# G.net
KiCad netlist of a schematic drawn in Altium Designer
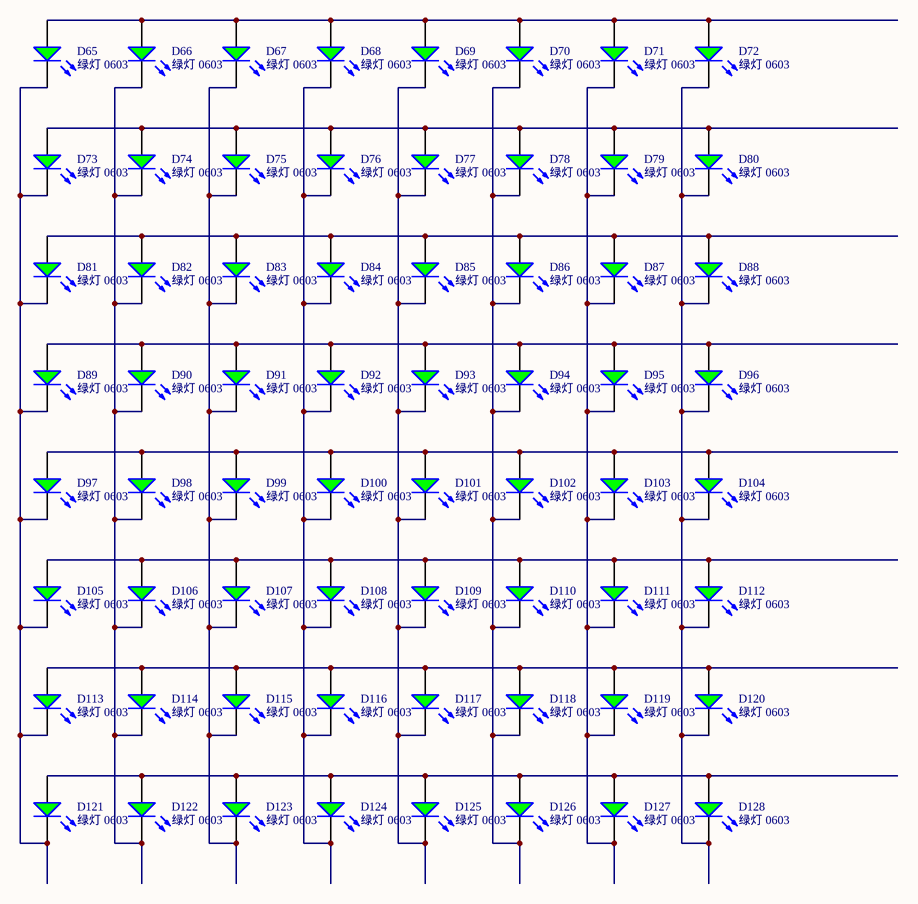
[diagram p0: G.SchDoc]

(export (version "E")
  (design (tool "Eeschema 10.0.6"))
  (components
    (comp (ref "D65")
      (value "绿灯 0603")
      (footprint "0603_LED_S1")
      (description "发光二极管")
      (libsource (lib "Miscellaneous Devices LC") (part "0603 绿灯"))
    )
    (comp (ref "D66")
      (value "绿灯 0603")
      (footprint "0603_LED_S1")
      (description "发光二极管")
      (libsource (lib "Miscellaneous Devices LC") (part "0603 绿灯"))
    )
    (comp (ref "D67")
      (value "绿灯 0603")
      (footprint "0603_LED_S1")
      (description "发光二极管")
      (libsource (lib "Miscellaneous Devices LC") (part "0603 绿灯"))
    )
    (comp (ref "D68")
      (value "绿灯 0603")
      (footprint "0603_LED_S1")
      (description "发光二极管")
      (libsource (lib "Miscellaneous Devices LC") (part "0603 绿灯"))
    )
    (comp (ref "D69")
      (value "绿灯 0603")
      (footprint "0603_LED_S1")
      (description "发光二极管")
      (libsource (lib "Miscellaneous Devices LC") (part "0603 绿灯"))
    )
    (comp (ref "D70")
      (value "绿灯 0603")
      (footprint "0603_LED_S1")
      (description "发光二极管")
      (libsource (lib "Miscellaneous Devices LC") (part "0603 绿灯"))
    )
    (comp (ref "D71")
      (value "绿灯 0603")
      (footprint "0603_LED_S1")
      (description "发光二极管")
      (libsource (lib "Miscellaneous Devices LC") (part "0603 绿灯"))
    )
    (comp (ref "D72")
      (value "绿灯 0603")
      (footprint "0603_LED_S1")
      (description "发光二极管")
      (libsource (lib "Miscellaneous Devices LC") (part "0603 绿灯"))
    )
    (comp (ref "D73")
      (value "绿灯 0603")
      (footprint "0603_LED_S1")
      (description "发光二极管")
      (libsource (lib "Miscellaneous Devices LC") (part "0603 绿灯"))
    )
    (comp (ref "D74")
      (value "绿灯 0603")
      (footprint "0603_LED_S1")
      (description "发光二极管")
      (libsource (lib "Miscellaneous Devices LC") (part "0603 绿灯"))
    )
    (comp (ref "D75")
      (value "绿灯 0603")
      (footprint "0603_LED_S1")
      (description "发光二极管")
      (libsource (lib "Miscellaneous Devices LC") (part "0603 绿灯"))
    )
    (comp (ref "D76")
      (value "绿灯 0603")
      (footprint "0603_LED_S1")
      (description "发光二极管")
      (libsource (lib "Miscellaneous Devices LC") (part "0603 绿灯"))
    )
    (comp (ref "D77")
      (value "绿灯 0603")
      (footprint "0603_LED_S1")
      (description "发光二极管")
      (libsource (lib "Miscellaneous Devices LC") (part "0603 绿灯"))
    )
    (comp (ref "D78")
      (value "绿灯 0603")
      (footprint "0603_LED_S1")
      (description "发光二极管")
      (libsource (lib "Miscellaneous Devices LC") (part "0603 绿灯"))
    )
    (comp (ref "D79")
      (value "绿灯 0603")
      (footprint "0603_LED_S1")
      (description "发光二极管")
      (libsource (lib "Miscellaneous Devices LC") (part "0603 绿灯"))
    )
    (comp (ref "D80")
      (value "绿灯 0603")
      (footprint "0603_LED_S1")
      (description "发光二极管")
      (libsource (lib "Miscellaneous Devices LC") (part "0603 绿灯"))
    )
    (comp (ref "D81")
      (value "绿灯 0603")
      (footprint "0603_LED_S1")
      (description "发光二极管")
      (libsource (lib "Miscellaneous Devices LC") (part "0603 绿灯"))
    )
    (comp (ref "D82")
      (value "绿灯 0603")
      (footprint "0603_LED_S1")
      (description "发光二极管")
      (libsource (lib "Miscellaneous Devices LC") (part "0603 绿灯"))
    )
    (comp (ref "D83")
      (value "绿灯 0603")
      (footprint "0603_LED_S1")
      (description "发光二极管")
      (libsource (lib "Miscellaneous Devices LC") (part "0603 绿灯"))
    )
    (comp (ref "D84")
      (value "绿灯 0603")
      (footprint "0603_LED_S1")
      (description "发光二极管")
      (libsource (lib "Miscellaneous Devices LC") (part "0603 绿灯"))
    )
    (comp (ref "D85")
      (value "绿灯 0603")
      (footprint "0603_LED_S1")
      (description "发光二极管")
      (libsource (lib "Miscellaneous Devices LC") (part "0603 绿灯"))
    )
    (comp (ref "D86")
      (value "绿灯 0603")
      (footprint "0603_LED_S1")
      (description "发光二极管")
      (libsource (lib "Miscellaneous Devices LC") (part "0603 绿灯"))
    )
    (comp (ref "D87")
      (value "绿灯 0603")
      (footprint "0603_LED_S1")
      (description "发光二极管")
      (libsource (lib "Miscellaneous Devices LC") (part "0603 绿灯"))
    )
    (comp (ref "D88")
      (value "绿灯 0603")
      (footprint "0603_LED_S1")
      (description "发光二极管")
      (libsource (lib "Miscellaneous Devices LC") (part "0603 绿灯"))
    )
    (comp (ref "D89")
      (value "绿灯 0603")
      (footprint "0603_LED_S1")
      (description "发光二极管")
      (libsource (lib "Miscellaneous Devices LC") (part "0603 绿灯"))
    )
    (comp (ref "D90")
      (value "绿灯 0603")
      (footprint "0603_LED_S1")
      (description "发光二极管")
      (libsource (lib "Miscellaneous Devices LC") (part "0603 绿灯"))
    )
    (comp (ref "D91")
      (value "绿灯 0603")
      (footprint "0603_LED_S1")
      (description "发光二极管")
      (libsource (lib "Miscellaneous Devices LC") (part "0603 绿灯"))
    )
    (comp (ref "D92")
      (value "绿灯 0603")
      (footprint "0603_LED_S1")
      (description "发光二极管")
      (libsource (lib "Miscellaneous Devices LC") (part "0603 绿灯"))
    )
    (comp (ref "D93")
      (value "绿灯 0603")
      (footprint "0603_LED_S1")
      (description "发光二极管")
      (libsource (lib "Miscellaneous Devices LC") (part "0603 绿灯"))
    )
    (comp (ref "D94")
      (value "绿灯 0603")
      (footprint "0603_LED_S1")
      (description "发光二极管")
      (libsource (lib "Miscellaneous Devices LC") (part "0603 绿灯"))
    )
    (comp (ref "D95")
      (value "绿灯 0603")
      (footprint "0603_LED_S1")
      (description "发光二极管")
      (libsource (lib "Miscellaneous Devices LC") (part "0603 绿灯"))
    )
    (comp (ref "D96")
      (value "绿灯 0603")
      (footprint "0603_LED_S1")
      (description "发光二极管")
      (libsource (lib "Miscellaneous Devices LC") (part "0603 绿灯"))
    )
    (comp (ref "D97")
      (value "绿灯 0603")
      (footprint "0603_LED_S1")
      (description "发光二极管")
      (libsource (lib "Miscellaneous Devices LC") (part "0603 绿灯"))
    )
    (comp (ref "D98")
      (value "绿灯 0603")
      (footprint "0603_LED_S1")
      (description "发光二极管")
      (libsource (lib "Miscellaneous Devices LC") (part "0603 绿灯"))
    )
    (comp (ref "D99")
      (value "绿灯 0603")
      (footprint "0603_LED_S1")
      (description "发光二极管")
      (libsource (lib "Miscellaneous Devices LC") (part "0603 绿灯"))
    )
    (comp (ref "D100")
      (value "绿灯 0603")
      (footprint "0603_LED_S1")
      (description "发光二极管")
      (libsource (lib "Miscellaneous Devices LC") (part "0603 绿灯"))
    )
    (comp (ref "D101")
      (value "绿灯 0603")
      (footprint "0603_LED_S1")
      (description "发光二极管")
      (libsource (lib "Miscellaneous Devices LC") (part "0603 绿灯"))
    )
    (comp (ref "D102")
      (value "绿灯 0603")
      (footprint "0603_LED_S1")
      (description "发光二极管")
      (libsource (lib "Miscellaneous Devices LC") (part "0603 绿灯"))
    )
    (comp (ref "D103")
      (value "绿灯 0603")
      (footprint "0603_LED_S1")
      (description "发光二极管")
      (libsource (lib "Miscellaneous Devices LC") (part "0603 绿灯"))
    )
    (comp (ref "D104")
      (value "绿灯 0603")
      (footprint "0603_LED_S1")
      (description "发光二极管")
      (libsource (lib "Miscellaneous Devices LC") (part "0603 绿灯"))
    )
    (comp (ref "D105")
      (value "绿灯 0603")
      (footprint "0603_LED_S1")
      (description "发光二极管")
      (libsource (lib "Miscellaneous Devices LC") (part "0603 绿灯"))
    )
    (comp (ref "D106")
      (value "绿灯 0603")
      (footprint "0603_LED_S1")
      (description "发光二极管")
      (libsource (lib "Miscellaneous Devices LC") (part "0603 绿灯"))
    )
    (comp (ref "D107")
      (value "绿灯 0603")
      (footprint "0603_LED_S1")
      (description "发光二极管")
      (libsource (lib "Miscellaneous Devices LC") (part "0603 绿灯"))
    )
    (comp (ref "D108")
      (value "绿灯 0603")
      (footprint "0603_LED_S1")
      (description "发光二极管")
      (libsource (lib "Miscellaneous Devices LC") (part "0603 绿灯"))
    )
    (comp (ref "D109")
      (value "绿灯 0603")
      (footprint "0603_LED_S1")
      (description "发光二极管")
      (libsource (lib "Miscellaneous Devices LC") (part "0603 绿灯"))
    )
    (comp (ref "D110")
      (value "绿灯 0603")
      (footprint "0603_LED_S1")
      (description "发光二极管")
      (libsource (lib "Miscellaneous Devices LC") (part "0603 绿灯"))
    )
    (comp (ref "D111")
      (value "绿灯 0603")
      (footprint "0603_LED_S1")
      (description "发光二极管")
      (libsource (lib "Miscellaneous Devices LC") (part "0603 绿灯"))
    )
    (comp (ref "D112")
      (value "绿灯 0603")
      (footprint "0603_LED_S1")
      (description "发光二极管")
      (libsource (lib "Miscellaneous Devices LC") (part "0603 绿灯"))
    )
    (comp (ref "D113")
      (value "绿灯 0603")
      (footprint "0603_LED_S1")
      (description "发光二极管")
      (libsource (lib "Miscellaneous Devices LC") (part "0603 绿灯"))
    )
    (comp (ref "D114")
      (value "绿灯 0603")
      (footprint "0603_LED_S1")
      (description "发光二极管")
      (libsource (lib "Miscellaneous Devices LC") (part "0603 绿灯"))
    )
    (comp (ref "D115")
      (value "绿灯 0603")
      (footprint "0603_LED_S1")
      (description "发光二极管")
      (libsource (lib "Miscellaneous Devices LC") (part "0603 绿灯"))
    )
    (comp (ref "D116")
      (value "绿灯 0603")
      (footprint "0603_LED_S1")
      (description "发光二极管")
      (libsource (lib "Miscellaneous Devices LC") (part "0603 绿灯"))
    )
    (comp (ref "D117")
      (value "绿灯 0603")
      (footprint "0603_LED_S1")
      (description "发光二极管")
      (libsource (lib "Miscellaneous Devices LC") (part "0603 绿灯"))
    )
    (comp (ref "D118")
      (value "绿灯 0603")
      (footprint "0603_LED_S1")
      (description "发光二极管")
      (libsource (lib "Miscellaneous Devices LC") (part "0603 绿灯"))
    )
    (comp (ref "D119")
      (value "绿灯 0603")
      (footprint "0603_LED_S1")
      (description "发光二极管")
      (libsource (lib "Miscellaneous Devices LC") (part "0603 绿灯"))
    )
    (comp (ref "D120")
      (value "绿灯 0603")
      (footprint "0603_LED_S1")
      (description "发光二极管")
      (libsource (lib "Miscellaneous Devices LC") (part "0603 绿灯"))
    )
    (comp (ref "D121")
      (value "绿灯 0603")
      (footprint "0603_LED_S1")
      (description "发光二极管")
      (libsource (lib "Miscellaneous Devices LC") (part "0603 绿灯"))
    )
    (comp (ref "D122")
      (value "绿灯 0603")
      (footprint "0603_LED_S1")
      (description "发光二极管")
      (libsource (lib "Miscellaneous Devices LC") (part "0603 绿灯"))
    )
    (comp (ref "D123")
      (value "绿灯 0603")
      (footprint "0603_LED_S1")
      (description "发光二极管")
      (libsource (lib "Miscellaneous Devices LC") (part "0603 绿灯"))
    )
    (comp (ref "D124")
      (value "绿灯 0603")
      (footprint "0603_LED_S1")
      (description "发光二极管")
      (libsource (lib "Miscellaneous Devices LC") (part "0603 绿灯"))
    )
    (comp (ref "D125")
      (value "绿灯 0603")
      (footprint "0603_LED_S1")
      (description "发光二极管")
      (libsource (lib "Miscellaneous Devices LC") (part "0603 绿灯"))
    )
    (comp (ref "D126")
      (value "绿灯 0603")
      (footprint "0603_LED_S1")
      (description "发光二极管")
      (libsource (lib "Miscellaneous Devices LC") (part "0603 绿灯"))
    )
    (comp (ref "D127")
      (value "绿灯 0603")
      (footprint "0603_LED_S1")
      (description "发光二极管")
      (libsource (lib "Miscellaneous Devices LC") (part "0603 绿灯"))
    )
    (comp (ref "D128")
      (value "绿灯 0603")
      (footprint "0603_LED_S1")
      (description "发光二极管")
      (libsource (lib "Miscellaneous Devices LC") (part "0603 绿灯"))
    )
  )
  (nets
    (net (code "1") (name "Net-(D65-PadA)") (class "Default")
      (node (ref "D65") (pin "A") (pinfunction "A_A") (pintype "passive"))
      (node (ref "D66") (pin "A") (pinfunction "A_A") (pintype "passive"))
      (node (ref "D67") (pin "A") (pinfunction "A_A") (pintype "passive"))
      (node (ref "D68") (pin "A") (pinfunction "A_A") (pintype "passive"))
      (node (ref "D69") (pin "A") (pinfunction "A_A") (pintype "passive"))
      (node (ref "D70") (pin "A") (pinfunction "A_A") (pintype "passive"))
      (node (ref "D71") (pin "A") (pinfunction "A_A") (pintype "passive"))
      (node (ref "D72") (pin "A") (pinfunction "A_A") (pintype "passive"))
    )
    (net (code "2") (name "Net-(D73-PadA)") (class "Default")
      (node (ref "D73") (pin "A") (pinfunction "A_A") (pintype "passive"))
      (node (ref "D74") (pin "A") (pinfunction "A_A") (pintype "passive"))
      (node (ref "D75") (pin "A") (pinfunction "A_A") (pintype "passive"))
      (node (ref "D76") (pin "A") (pinfunction "A_A") (pintype "passive"))
      (node (ref "D77") (pin "A") (pinfunction "A_A") (pintype "passive"))
      (node (ref "D78") (pin "A") (pinfunction "A_A") (pintype "passive"))
      (node (ref "D79") (pin "A") (pinfunction "A_A") (pintype "passive"))
      (node (ref "D80") (pin "A") (pinfunction "A_A") (pintype "passive"))
    )
    (net (code "3") (name "Net-(D81-PadA)") (class "Default")
      (node (ref "D81") (pin "A") (pinfunction "A_A") (pintype "passive"))
      (node (ref "D82") (pin "A") (pinfunction "A_A") (pintype "passive"))
      (node (ref "D83") (pin "A") (pinfunction "A_A") (pintype "passive"))
      (node (ref "D84") (pin "A") (pinfunction "A_A") (pintype "passive"))
      (node (ref "D85") (pin "A") (pinfunction "A_A") (pintype "passive"))
      (node (ref "D86") (pin "A") (pinfunction "A_A") (pintype "passive"))
      (node (ref "D87") (pin "A") (pinfunction "A_A") (pintype "passive"))
      (node (ref "D88") (pin "A") (pinfunction "A_A") (pintype "passive"))
    )
    (net (code "4") (name "Net-(D89-PadA)") (class "Default")
      (node (ref "D89") (pin "A") (pinfunction "A_A") (pintype "passive"))
      (node (ref "D90") (pin "A") (pinfunction "A_A") (pintype "passive"))
      (node (ref "D91") (pin "A") (pinfunction "A_A") (pintype "passive"))
      (node (ref "D92") (pin "A") (pinfunction "A_A") (pintype "passive"))
      (node (ref "D93") (pin "A") (pinfunction "A_A") (pintype "passive"))
      (node (ref "D94") (pin "A") (pinfunction "A_A") (pintype "passive"))
      (node (ref "D95") (pin "A") (pinfunction "A_A") (pintype "passive"))
      (node (ref "D96") (pin "A") (pinfunction "A_A") (pintype "passive"))
    )
    (net (code "5") (name "Net-(D100-PadA)") (class "Default")
      (node (ref "D100") (pin "A") (pinfunction "A_A") (pintype "passive"))
      (node (ref "D101") (pin "A") (pinfunction "A_A") (pintype "passive"))
      (node (ref "D102") (pin "A") (pinfunction "A_A") (pintype "passive"))
      (node (ref "D103") (pin "A") (pinfunction "A_A") (pintype "passive"))
      (node (ref "D104") (pin "A") (pinfunction "A_A") (pintype "passive"))
      (node (ref "D97") (pin "A") (pinfunction "A_A") (pintype "passive"))
      (node (ref "D98") (pin "A") (pinfunction "A_A") (pintype "passive"))
      (node (ref "D99") (pin "A") (pinfunction "A_A") (pintype "passive"))
    )
    (net (code "6") (name "Net-(D100-PadK)") (class "Default")
      (node (ref "D100") (pin "K") (pinfunction "K_K") (pintype "passive"))
      (node (ref "D108") (pin "K") (pinfunction "K_K") (pintype "passive"))
      (node (ref "D116") (pin "K") (pinfunction "K_K") (pintype "passive"))
      (node (ref "D124") (pin "K") (pinfunction "K_K") (pintype "passive"))
      (node (ref "D68") (pin "K") (pinfunction "K_K") (pintype "passive"))
      (node (ref "D76") (pin "K") (pinfunction "K_K") (pintype "passive"))
      (node (ref "D84") (pin "K") (pinfunction "K_K") (pintype "passive"))
      (node (ref "D92") (pin "K") (pinfunction "K_K") (pintype "passive"))
    )
    (net (code "7") (name "Net-(D101-PadK)") (class "Default")
      (node (ref "D101") (pin "K") (pinfunction "K_K") (pintype "passive"))
      (node (ref "D109") (pin "K") (pinfunction "K_K") (pintype "passive"))
      (node (ref "D117") (pin "K") (pinfunction "K_K") (pintype "passive"))
      (node (ref "D125") (pin "K") (pinfunction "K_K") (pintype "passive"))
      (node (ref "D69") (pin "K") (pinfunction "K_K") (pintype "passive"))
      (node (ref "D77") (pin "K") (pinfunction "K_K") (pintype "passive"))
      (node (ref "D85") (pin "K") (pinfunction "K_K") (pintype "passive"))
      (node (ref "D93") (pin "K") (pinfunction "K_K") (pintype "passive"))
    )
    (net (code "8") (name "Net-(D102-PadK)") (class "Default")
      (node (ref "D102") (pin "K") (pinfunction "K_K") (pintype "passive"))
      (node (ref "D110") (pin "K") (pinfunction "K_K") (pintype "passive"))
      (node (ref "D118") (pin "K") (pinfunction "K_K") (pintype "passive"))
      (node (ref "D126") (pin "K") (pinfunction "K_K") (pintype "passive"))
      (node (ref "D70") (pin "K") (pinfunction "K_K") (pintype "passive"))
      (node (ref "D78") (pin "K") (pinfunction "K_K") (pintype "passive"))
      (node (ref "D86") (pin "K") (pinfunction "K_K") (pintype "passive"))
      (node (ref "D94") (pin "K") (pinfunction "K_K") (pintype "passive"))
    )
    (net (code "9") (name "Net-(D103-PadK)") (class "Default")
      (node (ref "D103") (pin "K") (pinfunction "K_K") (pintype "passive"))
      (node (ref "D111") (pin "K") (pinfunction "K_K") (pintype "passive"))
      (node (ref "D119") (pin "K") (pinfunction "K_K") (pintype "passive"))
      (node (ref "D127") (pin "K") (pinfunction "K_K") (pintype "passive"))
      (node (ref "D71") (pin "K") (pinfunction "K_K") (pintype "passive"))
      (node (ref "D79") (pin "K") (pinfunction "K_K") (pintype "passive"))
      (node (ref "D87") (pin "K") (pinfunction "K_K") (pintype "passive"))
      (node (ref "D95") (pin "K") (pinfunction "K_K") (pintype "passive"))
    )
    (net (code "10") (name "Net-(D104-PadK)") (class "Default")
      (node (ref "D104") (pin "K") (pinfunction "K_K") (pintype "passive"))
      (node (ref "D112") (pin "K") (pinfunction "K_K") (pintype "passive"))
      (node (ref "D120") (pin "K") (pinfunction "K_K") (pintype "passive"))
      (node (ref "D128") (pin "K") (pinfunction "K_K") (pintype "passive"))
      (node (ref "D72") (pin "K") (pinfunction "K_K") (pintype "passive"))
      (node (ref "D80") (pin "K") (pinfunction "K_K") (pintype "passive"))
      (node (ref "D88") (pin "K") (pinfunction "K_K") (pintype "passive"))
      (node (ref "D96") (pin "K") (pinfunction "K_K") (pintype "passive"))
    )
    (net (code "11") (name "Net-(D105-PadA)") (class "Default")
      (node (ref "D105") (pin "A") (pinfunction "A_A") (pintype "passive"))
      (node (ref "D106") (pin "A") (pinfunction "A_A") (pintype "passive"))
      (node (ref "D107") (pin "A") (pinfunction "A_A") (pintype "passive"))
      (node (ref "D108") (pin "A") (pinfunction "A_A") (pintype "passive"))
      (node (ref "D109") (pin "A") (pinfunction "A_A") (pintype "passive"))
      (node (ref "D110") (pin "A") (pinfunction "A_A") (pintype "passive"))
      (node (ref "D111") (pin "A") (pinfunction "A_A") (pintype "passive"))
      (node (ref "D112") (pin "A") (pinfunction "A_A") (pintype "passive"))
    )
    (net (code "12") (name "Net-(D105-PadK)") (class "Default")
      (node (ref "D105") (pin "K") (pinfunction "K_K") (pintype "passive"))
      (node (ref "D113") (pin "K") (pinfunction "K_K") (pintype "passive"))
      (node (ref "D121") (pin "K") (pinfunction "K_K") (pintype "passive"))
      (node (ref "D65") (pin "K") (pinfunction "K_K") (pintype "passive"))
      (node (ref "D73") (pin "K") (pinfunction "K_K") (pintype "passive"))
      (node (ref "D81") (pin "K") (pinfunction "K_K") (pintype "passive"))
      (node (ref "D89") (pin "K") (pinfunction "K_K") (pintype "passive"))
      (node (ref "D97") (pin "K") (pinfunction "K_K") (pintype "passive"))
    )
    (net (code "13") (name "Net-(D106-PadK)") (class "Default")
      (node (ref "D106") (pin "K") (pinfunction "K_K") (pintype "passive"))
      (node (ref "D114") (pin "K") (pinfunction "K_K") (pintype "passive"))
      (node (ref "D122") (pin "K") (pinfunction "K_K") (pintype "passive"))
      (node (ref "D66") (pin "K") (pinfunction "K_K") (pintype "passive"))
      (node (ref "D74") (pin "K") (pinfunction "K_K") (pintype "passive"))
      (node (ref "D82") (pin "K") (pinfunction "K_K") (pintype "passive"))
      (node (ref "D90") (pin "K") (pinfunction "K_K") (pintype "passive"))
      (node (ref "D98") (pin "K") (pinfunction "K_K") (pintype "passive"))
    )
    (net (code "14") (name "Net-(D107-PadK)") (class "Default")
      (node (ref "D107") (pin "K") (pinfunction "K_K") (pintype "passive"))
      (node (ref "D115") (pin "K") (pinfunction "K_K") (pintype "passive"))
      (node (ref "D123") (pin "K") (pinfunction "K_K") (pintype "passive"))
      (node (ref "D67") (pin "K") (pinfunction "K_K") (pintype "passive"))
      (node (ref "D75") (pin "K") (pinfunction "K_K") (pintype "passive"))
      (node (ref "D83") (pin "K") (pinfunction "K_K") (pintype "passive"))
      (node (ref "D91") (pin "K") (pinfunction "K_K") (pintype "passive"))
      (node (ref "D99") (pin "K") (pinfunction "K_K") (pintype "passive"))
    )
    (net (code "15") (name "Net-(D113-PadA)") (class "Default")
      (node (ref "D113") (pin "A") (pinfunction "A_A") (pintype "passive"))
      (node (ref "D114") (pin "A") (pinfunction "A_A") (pintype "passive"))
      (node (ref "D115") (pin "A") (pinfunction "A_A") (pintype "passive"))
      (node (ref "D116") (pin "A") (pinfunction "A_A") (pintype "passive"))
      (node (ref "D117") (pin "A") (pinfunction "A_A") (pintype "passive"))
      (node (ref "D118") (pin "A") (pinfunction "A_A") (pintype "passive"))
      (node (ref "D119") (pin "A") (pinfunction "A_A") (pintype "passive"))
      (node (ref "D120") (pin "A") (pinfunction "A_A") (pintype "passive"))
    )
    (net (code "16") (name "Net-(D121-PadA)") (class "Default")
      (node (ref "D121") (pin "A") (pinfunction "A_A") (pintype "passive"))
      (node (ref "D122") (pin "A") (pinfunction "A_A") (pintype "passive"))
      (node (ref "D123") (pin "A") (pinfunction "A_A") (pintype "passive"))
      (node (ref "D124") (pin "A") (pinfunction "A_A") (pintype "passive"))
      (node (ref "D125") (pin "A") (pinfunction "A_A") (pintype "passive"))
      (node (ref "D126") (pin "A") (pinfunction "A_A") (pintype "passive"))
      (node (ref "D127") (pin "A") (pinfunction "A_A") (pintype "passive"))
      (node (ref "D128") (pin "A") (pinfunction "A_A") (pintype "passive"))
    )
  )
)
